# APRSTracker.net
KiCad netlist of a schematic drawn in EAGLE
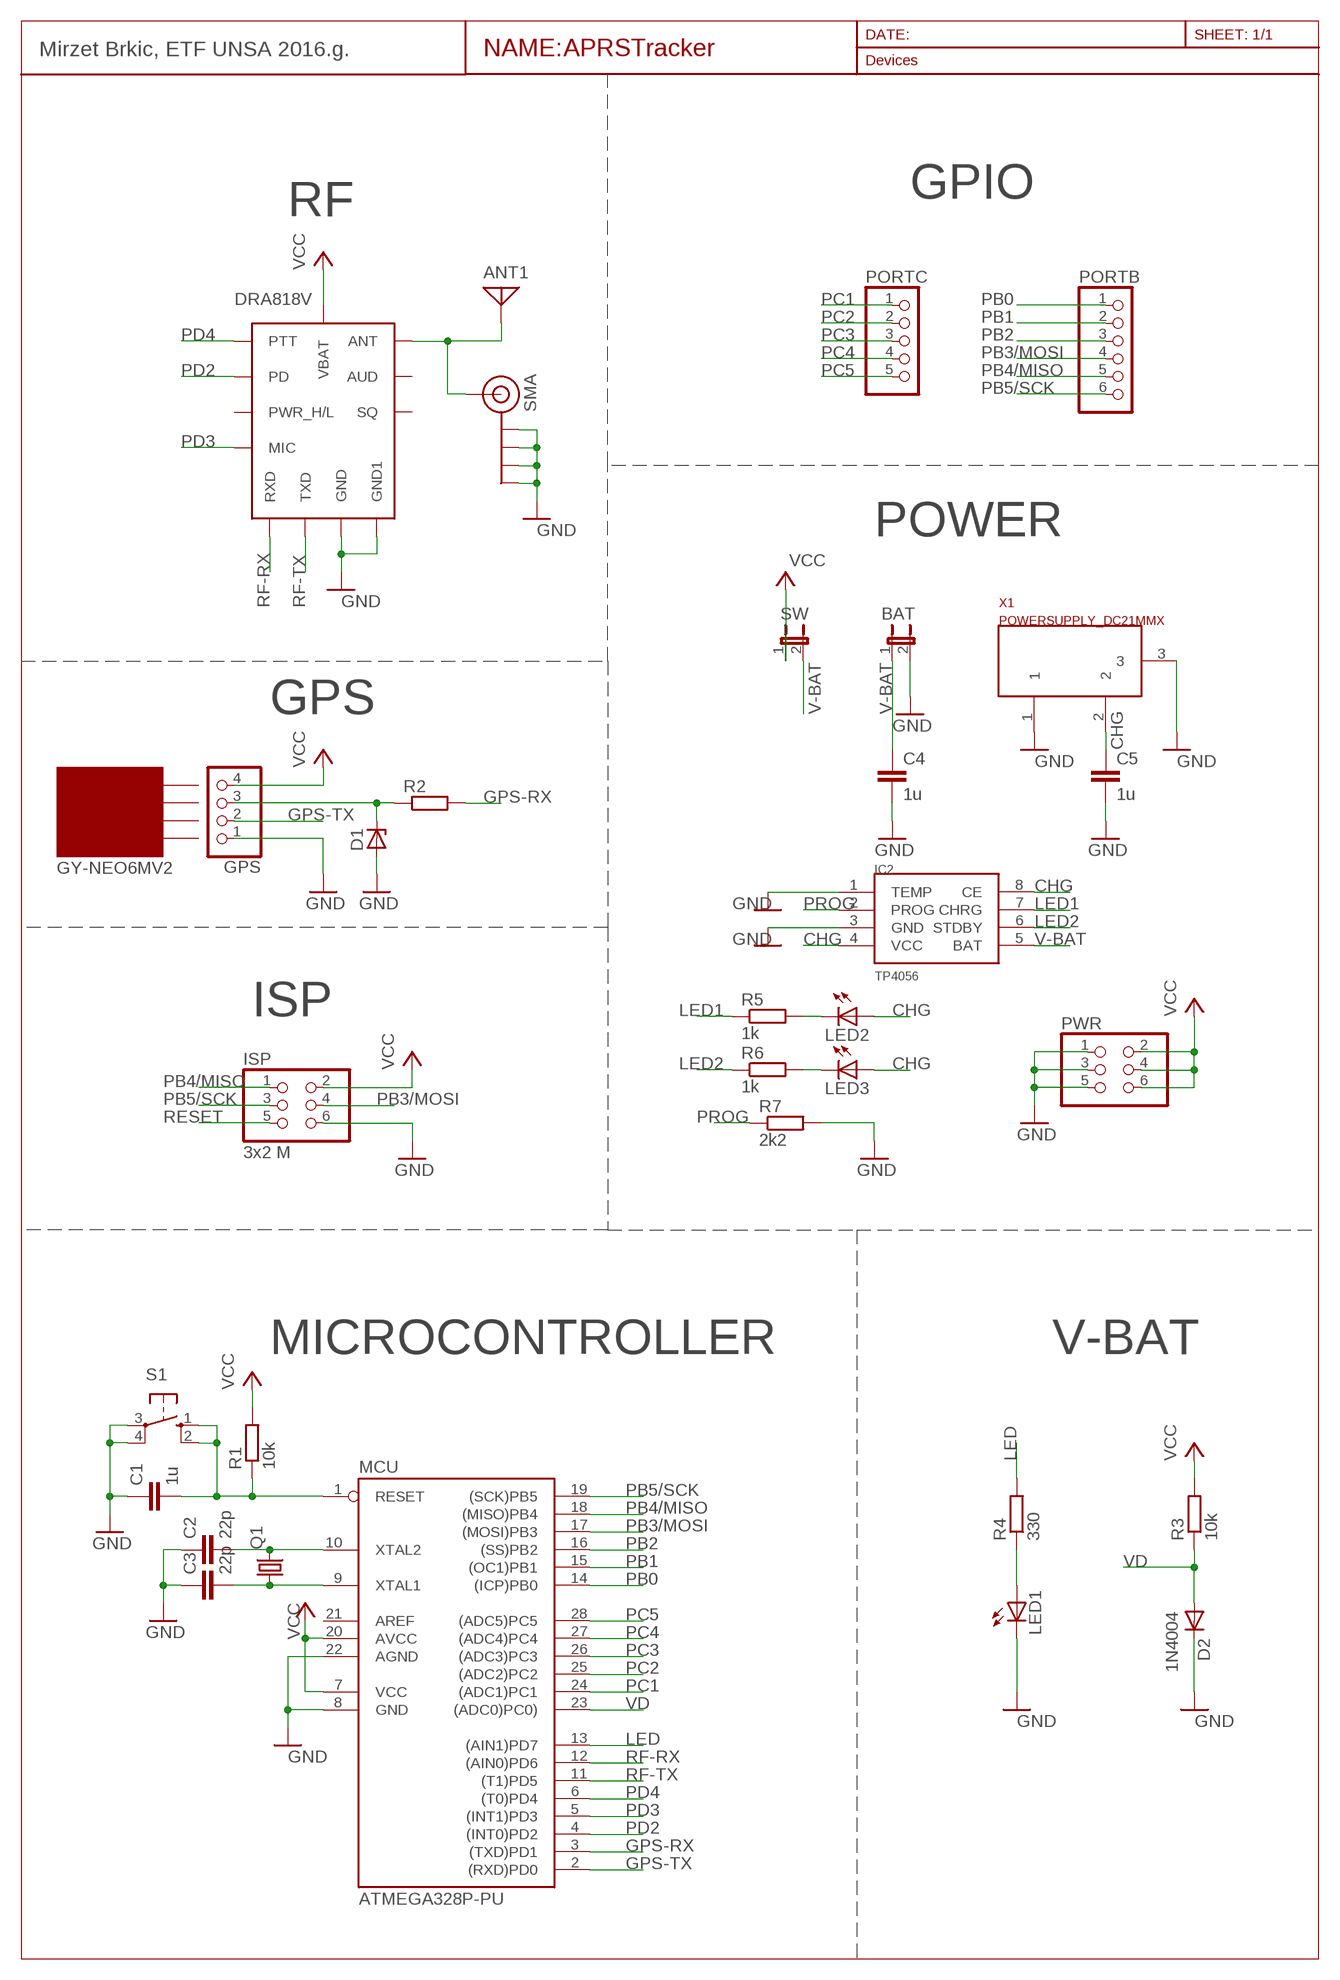
[diagram p0: schematic, sheet 1]

(export (version "E")
  (design (tool "Eeschema 10.0.6"))
  (components
    (comp (ref "ANT1")
      (value "ANTENNA")
      (footprint "eagle-import:PAD-01")
      (libsource (lib "eagle-import") (part "ANTENNA"))
    )
    (comp (ref "BAT")
      (value "JP1E")
      (footprint "eagle-import:JP1")
      (libsource (lib "eagle-import") (part "JP1E"))
    )
    (comp (ref "C1")
      (value "1u")
      (footprint "eagle-import:C050-024X044")
      (libsource (lib "eagle-import") (part "C-EU050-024X044"))
    )
    (comp (ref "C2")
      (value "22p")
      (footprint "eagle-import:C025-024X044")
      (libsource (lib "eagle-import") (part "C-EU025-024X044"))
    )
    (comp (ref "C3")
      (value "22p")
      (footprint "eagle-import:C025-024X044")
      (libsource (lib "eagle-import") (part "C-EU025-024X044"))
    )
    (comp (ref "C4")
      (value "1u")
      (footprint "eagle-import:C050-024X044")
      (libsource (lib "eagle-import") (part "C-EU050-024X044"))
    )
    (comp (ref "C5")
      (value "1u")
      (footprint "eagle-import:C050-024X044")
      (libsource (lib "eagle-import") (part "C-EU050-024X044"))
    )
    (comp (ref "D1")
      (value "ZENER-DIODEDO35Z10")
      (footprint "eagle-import:DO35Z10")
      (libsource (lib "eagle-import") (part "ZENER-DIODEDO35Z10"))
    )
    (comp (ref "D2")
      (value "1N4004")
      (footprint "eagle-import:DO41-10")
      (libsource (lib "eagle-import") (part "1N4004"))
    )
    (comp (ref "DRA818V")
      (value "DRA818V")
      (footprint "eagle-import:DRA8XXZ")
      (libsource (lib "eagle-import") (part "DRA818V"))
    )
    (comp (ref "GPS")
      (value "PINHD-1X4")
      (footprint "eagle-import:1X04")
      (libsource (lib "eagle-import") (part "PINHD-1X4"))
    )
    (comp (ref "IC2")
      (value "TP4056")
      (footprint "eagle-import:SOP-8")
      (libsource (lib "eagle-import") (part "TP4056"))
    )
    (comp (ref "ISP")
      (value "3x2 M")
      (footprint "eagle-import:2X03")
      (libsource (lib "eagle-import") (part "PINHD-2X3"))
    )
    (comp (ref "LED1")
      (value "LED3MM")
      (footprint "eagle-import:LED3MM")
      (libsource (lib "eagle-import") (part "LED3MM"))
    )
    (comp (ref "LED2")
      (value "LED3MM")
      (footprint "eagle-import:LED3MM")
      (libsource (lib "eagle-import") (part "LED3MM"))
    )
    (comp (ref "LED3")
      (value "LED3MM")
      (footprint "eagle-import:LED3MM")
      (libsource (lib "eagle-import") (part "LED3MM"))
    )
    (comp (ref "MCU")
      (value "ATMEGA328P-PU")
      (footprint "eagle-import:DIL28-3")
      (libsource (lib "eagle-import") (part "ATMEGA328P-PU"))
    )
    (comp (ref "PORTB")
      (value "PINHD-1X6")
      (footprint "eagle-import:1X06")
      (libsource (lib "eagle-import") (part "PINHD-1X6"))
    )
    (comp (ref "PORTC")
      (value "PINHD-1X5")
      (footprint "eagle-import:1X05")
      (libsource (lib "eagle-import") (part "PINHD-1X5"))
    )
    (comp (ref "PWR")
      (value "PINHD-2X3")
      (footprint "eagle-import:2X03")
      (libsource (lib "eagle-import") (part "pinhead_PINHD-2X3"))
    )
    (comp (ref "Q1")
      (value "CRYSTALHC49S")
      (footprint "eagle-import:HC49_S")
      (libsource (lib "eagle-import") (part "CRYSTALHC49S"))
    )
    (comp (ref "R1")
      (value "10k")
      (footprint "eagle-import:0207_10")
      (libsource (lib "eagle-import") (part "R-EU_0207/10"))
    )
    (comp (ref "R2")
      (value "R-EU_0207/10")
      (footprint "eagle-import:0207_10")
      (libsource (lib "eagle-import") (part "R-EU_0207/10"))
    )
    (comp (ref "R3")
      (value "10k")
      (footprint "eagle-import:0207_10")
      (libsource (lib "eagle-import") (part "R-EU_0207/10"))
    )
    (comp (ref "R4")
      (value "330")
      (footprint "eagle-import:0207_10")
      (libsource (lib "eagle-import") (part "R-EU_0207/10"))
    )
    (comp (ref "R5")
      (value "1k")
      (footprint "eagle-import:0207_10")
      (libsource (lib "eagle-import") (part "R-EU_0207/10"))
    )
    (comp (ref "R6")
      (value "1k")
      (footprint "eagle-import:0207_10")
      (libsource (lib "eagle-import") (part "R-EU_0207/10"))
    )
    (comp (ref "R7")
      (value "2k2")
      (footprint "eagle-import:0207_10")
      (libsource (lib "eagle-import") (part "R-EU_0207/10"))
    )
    (comp (ref "S1")
      (value "10-XX")
      (footprint "eagle-import:B3F-10XX")
      (fields (field (name "MPN") "B3F-1000"))
      (libsource (lib "eagle-import") (part "10-XX"))
    )
    (comp (ref "SMA")
      (value "SMA_EDGE")
      (footprint "eagle-import:SMA-EDGE")
      (libsource (lib "eagle-import") (part "SMA_EDGE"))
    )
    (comp (ref "SW")
      (value "JP1E")
      (footprint "eagle-import:JP1")
      (libsource (lib "eagle-import") (part "JP1E"))
    )
    (comp (ref "X1")
      (value "POWERSUPPLY_DC21MMX")
      (footprint "eagle-import:POWERSUPPLY_DC-21MM")
      (libsource (lib "eagle-import") (part "POWERSUPPLY_DC21MMX"))
    )
  )
  (nets
    (net (code "1") (name "/CHG") (class "Default")
      (node (ref "C5") (pin "1") (pinfunction "1_1") (pintype "passive"))
      (node (ref "IC2") (pin "4") (pinfunction "VCC_4") (pintype "bidirectional"))
      (node (ref "IC2") (pin "8") (pinfunction "CE_8") (pintype "bidirectional"))
      (node (ref "LED2") (pin "A") (pinfunction "A_A") (pintype "passive"))
      (node (ref "LED3") (pin "A") (pinfunction "A_A") (pintype "passive"))
      (node (ref "X1") (pin "2") (pinfunction "2_2") (pintype "power_in"))
    )
    (net (code "2") (name "/GPS-RX") (class "Default")
      (node (ref "MCU") (pin "3") (pinfunction "(TXD)PD1_3") (pintype "bidirectional"))
      (node (ref "R2") (pin "2") (pinfunction "2_2") (pintype "passive"))
    )
    (net (code "3") (name "/GPS-TX") (class "Default")
      (node (ref "GPS") (pin "2") (pinfunction "2_2") (pintype "passive"))
      (node (ref "MCU") (pin "2") (pinfunction "(RXD)PD0_2") (pintype "bidirectional"))
    )
    (net (code "4") (name "/LED") (class "Default")
      (node (ref "MCU") (pin "13") (pinfunction "(AIN1)PD7_13") (pintype "bidirectional"))
      (node (ref "R4") (pin "2") (pinfunction "2_2") (pintype "passive"))
    )
    (net (code "5") (name "/LED1") (class "Default")
      (node (ref "IC2") (pin "7") (pinfunction "CHRG_7") (pintype "bidirectional"))
      (node (ref "R5") (pin "1") (pinfunction "1_1") (pintype "passive"))
    )
    (net (code "6") (name "/LED2") (class "Default")
      (node (ref "IC2") (pin "6") (pinfunction "STDBY_6") (pintype "bidirectional"))
      (node (ref "R6") (pin "1") (pinfunction "1_1") (pintype "passive"))
    )
    (net (code "7") (name "/PB0") (class "Default")
      (node (ref "MCU") (pin "14") (pinfunction "(ICP)PB0_14") (pintype "bidirectional"))
      (node (ref "PORTB") (pin "1") (pinfunction "1_1") (pintype "passive"))
    )
    (net (code "8") (name "/PB1") (class "Default")
      (node (ref "MCU") (pin "15") (pinfunction "(OC1)PB1_15") (pintype "bidirectional"))
      (node (ref "PORTB") (pin "2") (pinfunction "2_2") (pintype "passive"))
    )
    (net (code "9") (name "/PB2") (class "Default")
      (node (ref "MCU") (pin "16") (pinfunction "(SS)PB2_16") (pintype "bidirectional"))
      (node (ref "PORTB") (pin "3") (pinfunction "3_3") (pintype "passive"))
    )
    (net (code "10") (name "/PB3{slash}MOSI") (class "Default")
      (node (ref "ISP") (pin "4") (pinfunction "4_4") (pintype "passive"))
      (node (ref "MCU") (pin "17") (pinfunction "(MOSI)PB3_17") (pintype "bidirectional"))
      (node (ref "PORTB") (pin "4") (pinfunction "4_4") (pintype "passive"))
    )
    (net (code "11") (name "/PB4{slash}MISO") (class "Default")
      (node (ref "ISP") (pin "1") (pinfunction "1_1") (pintype "passive"))
      (node (ref "MCU") (pin "18") (pinfunction "(MISO)PB4_18") (pintype "bidirectional"))
      (node (ref "PORTB") (pin "5") (pinfunction "5_5") (pintype "passive"))
    )
    (net (code "12") (name "/PB5{slash}SCK") (class "Default")
      (node (ref "ISP") (pin "3") (pinfunction "3_3") (pintype "passive"))
      (node (ref "MCU") (pin "19") (pinfunction "(SCK)PB5_19") (pintype "bidirectional"))
      (node (ref "PORTB") (pin "6") (pinfunction "6_6") (pintype "passive"))
    )
    (net (code "13") (name "/PC1") (class "Default")
      (node (ref "MCU") (pin "24") (pinfunction "(ADC1)PC1_24") (pintype "bidirectional"))
      (node (ref "PORTC") (pin "1") (pinfunction "1_1") (pintype "passive"))
    )
    (net (code "14") (name "/PC2") (class "Default")
      (node (ref "MCU") (pin "25") (pinfunction "(ADC2)PC2_25") (pintype "bidirectional"))
      (node (ref "PORTC") (pin "2") (pinfunction "2_2") (pintype "passive"))
    )
    (net (code "15") (name "/PC3") (class "Default")
      (node (ref "MCU") (pin "26") (pinfunction "(ADC3)PC3_26") (pintype "bidirectional"))
      (node (ref "PORTC") (pin "3") (pinfunction "3_3") (pintype "passive"))
    )
    (net (code "16") (name "/PC4") (class "Default")
      (node (ref "MCU") (pin "27") (pinfunction "(ADC4)PC4_27") (pintype "bidirectional"))
      (node (ref "PORTC") (pin "4") (pinfunction "4_4") (pintype "passive"))
    )
    (net (code "17") (name "/PC5") (class "Default")
      (node (ref "MCU") (pin "28") (pinfunction "(ADC5)PC5_28") (pintype "bidirectional"))
      (node (ref "PORTC") (pin "5") (pinfunction "5_5") (pintype "passive"))
    )
    (net (code "18") (name "/PD2") (class "Default")
      (node (ref "DRA818V") (pin "P$6") (pinfunction "PD_P$6") (pintype "bidirectional"))
      (node (ref "MCU") (pin "4") (pinfunction "(INT0)PD2_4") (pintype "bidirectional"))
    )
    (net (code "19") (name "/PD3") (class "Default")
      (node (ref "DRA818V") (pin "P$18") (pinfunction "MIC_P$18") (pintype "bidirectional"))
      (node (ref "MCU") (pin "5") (pinfunction "(INT1)PD3_5") (pintype "bidirectional"))
    )
    (net (code "20") (name "/PD4") (class "Default")
      (node (ref "DRA818V") (pin "P$5") (pinfunction "PTT_P$5") (pintype "bidirectional"))
      (node (ref "MCU") (pin "6") (pinfunction "(T0)PD4_6") (pintype "bidirectional"))
    )
    (net (code "21") (name "/PROG") (class "Default")
      (node (ref "IC2") (pin "2") (pinfunction "PROG_2") (pintype "bidirectional"))
      (node (ref "R7") (pin "1") (pinfunction "1_1") (pintype "passive"))
    )
    (net (code "22") (name "/RESET") (class "Default")
      (node (ref "C1") (pin "2") (pinfunction "2_2") (pintype "passive"))
      (node (ref "ISP") (pin "5") (pinfunction "5_5") (pintype "passive"))
      (node (ref "MCU") (pin "1") (pinfunction "RESET_1") (pintype "input"))
      (node (ref "R1") (pin "1") (pinfunction "1_1") (pintype "passive"))
      (node (ref "S1") (pin "1") (pinfunction "S_1") (pintype "passive"))
      (node (ref "S1") (pin "2") (pinfunction "S1_2") (pintype "passive"))
    )
    (net (code "23") (name "/RF-RX") (class "Default")
      (node (ref "DRA818V") (pin "P$16") (pinfunction "RXD_P$16") (pintype "bidirectional"))
      (node (ref "MCU") (pin "12") (pinfunction "(AIN0)PD6_12") (pintype "bidirectional"))
    )
    (net (code "24") (name "/RF-TX") (class "Default")
      (node (ref "DRA818V") (pin "P$17") (pinfunction "TXD_P$17") (pintype "bidirectional"))
      (node (ref "MCU") (pin "11") (pinfunction "(T1)PD5_11") (pintype "bidirectional"))
    )
    (net (code "25") (name "/V-BAT") (class "Default")
      (node (ref "BAT") (pin "1") (pinfunction "1_1") (pintype "passive"))
      (node (ref "C4") (pin "1") (pinfunction "1_1") (pintype "passive"))
      (node (ref "IC2") (pin "5") (pinfunction "BAT_5") (pintype "bidirectional"))
      (node (ref "SW") (pin "2") (pinfunction "2_2") (pintype "passive"))
    )
    (net (code "26") (name "/VD") (class "Default")
      (node (ref "D2") (pin "A") (pinfunction "A_A") (pintype "passive"))
      (node (ref "MCU") (pin "23") (pinfunction "(ADC0)PC0)_23") (pintype "bidirectional"))
      (node (ref "R3") (pin "1") (pinfunction "1_1") (pintype "passive"))
    )
    (net (code "27") (name "GND") (class "Default")
      (node (ref "BAT") (pin "2") (pinfunction "2_2") (pintype "passive"))
      (node (ref "C1") (pin "1") (pinfunction "1_1") (pintype "passive"))
      (node (ref "C2") (pin "1") (pinfunction "1_1") (pintype "passive"))
      (node (ref "C3") (pin "1") (pinfunction "1_1") (pintype "passive"))
      (node (ref "C4") (pin "2") (pinfunction "2_2") (pintype "passive"))
      (node (ref "C5") (pin "2") (pinfunction "2_2") (pintype "passive"))
      (node (ref "D1") (pin "A") (pinfunction "A_A") (pintype "passive"))
      (node (ref "D2") (pin "C") (pinfunction "C_C") (pintype "passive"))
      (node (ref "DRA818V") (pin "P$10") (pinfunction "GND1_P$10") (pintype "bidirectional"))
      (node (ref "DRA818V") (pin "P$9") (pinfunction "GND_P$9") (pintype "bidirectional"))
      (node (ref "GPS") (pin "1") (pinfunction "1_1") (pintype "passive"))
      (node (ref "IC2") (pin "1") (pinfunction "TEMP_1") (pintype "bidirectional"))
      (node (ref "IC2") (pin "3") (pinfunction "GND_3") (pintype "bidirectional"))
      (node (ref "ISP") (pin "6") (pinfunction "6_6") (pintype "passive"))
      (node (ref "LED1") (pin "K") (pinfunction "C_K") (pintype "passive"))
      (node (ref "MCU") (pin "22") (pinfunction "AGND_22") (pintype "power_in"))
      (node (ref "MCU") (pin "8") (pinfunction "GND_8") (pintype "power_in"))
      (node (ref "PWR") (pin "1") (pinfunction "1_1") (pintype "passive"))
      (node (ref "PWR") (pin "3") (pinfunction "3_3") (pintype "passive"))
      (node (ref "PWR") (pin "5") (pinfunction "5_5") (pintype "passive"))
      (node (ref "R7") (pin "2") (pinfunction "2_2") (pintype "passive"))
      (node (ref "S1") (pin "3") (pinfunction "P_3") (pintype "passive"))
      (node (ref "S1") (pin "4") (pinfunction "P1_4") (pintype "passive"))
      (node (ref "SMA") (pin "GND@0") (pinfunction "GND_GND@0") (pintype "bidirectional"))
      (node (ref "SMA") (pin "GND@1") (pinfunction "GND_GND@1") (pintype "bidirectional"))
      (node (ref "SMA") (pin "GND@2") (pinfunction "GND_GND@2") (pintype "bidirectional"))
      (node (ref "SMA") (pin "GND@3") (pinfunction "GND_GND@3") (pintype "bidirectional"))
      (node (ref "X1") (pin "1") (pinfunction "1_1") (pintype "power_in"))
      (node (ref "X1") (pin "3") (pinfunction "3_3") (pintype "power_in"))
    )
    (net (code "28") (name "Net-(D1-PadC)") (class "Default")
      (node (ref "D1") (pin "C") (pinfunction "C_C") (pintype "passive"))
      (node (ref "GPS") (pin "3") (pinfunction "3_3") (pintype "passive"))
      (node (ref "R2") (pin "1") (pinfunction "1_1") (pintype "passive"))
    )
    (net (code "29") (name "Net-(DRA818V-ANT)") (class "Default")
      (node (ref "ANT1") (pin "1") (pinfunction "1_1") (pintype "output"))
      (node (ref "DRA818V") (pin "P$12") (pinfunction "ANT_P$12") (pintype "bidirectional"))
      (node (ref "SMA") (pin "SIG") (pinfunction "SIGNAL_SIG") (pintype "bidirectional"))
    )
    (net (code "30") (name "Net-(LED1-PadA)") (class "Default")
      (node (ref "LED1") (pin "A") (pinfunction "A_A") (pintype "passive"))
      (node (ref "R4") (pin "1") (pinfunction "1_1") (pintype "passive"))
    )
    (net (code "31") (name "Net-(LED2-C)") (class "Default")
      (node (ref "LED2") (pin "K") (pinfunction "C_K") (pintype "passive"))
      (node (ref "R5") (pin "2") (pinfunction "2_2") (pintype "passive"))
    )
    (net (code "32") (name "Net-(LED3-C)") (class "Default")
      (node (ref "LED3") (pin "K") (pinfunction "C_K") (pintype "passive"))
      (node (ref "R6") (pin "2") (pinfunction "2_2") (pintype "passive"))
    )
    (net (code "33") (name "Net-(MCU-XTAL1)") (class "Default")
      (node (ref "C3") (pin "2") (pinfunction "2_2") (pintype "passive"))
      (node (ref "MCU") (pin "9") (pinfunction "XTAL1_9") (pintype "bidirectional"))
      (node (ref "Q1") (pin "1") (pinfunction "1_1") (pintype "passive"))
    )
    (net (code "34") (name "Net-(MCU-XTAL2)") (class "Default")
      (node (ref "C2") (pin "2") (pinfunction "2_2") (pintype "passive"))
      (node (ref "MCU") (pin "10") (pinfunction "XTAL2_10") (pintype "bidirectional"))
      (node (ref "Q1") (pin "2") (pinfunction "2_2") (pintype "passive"))
    )
    (net (code "35") (name "VCC") (class "Default")
      (node (ref "DRA818V") (pin "P$8") (pinfunction "VBAT_P$8") (pintype "bidirectional"))
      (node (ref "GPS") (pin "4") (pinfunction "4_4") (pintype "passive"))
      (node (ref "ISP") (pin "2") (pinfunction "2_2") (pintype "passive"))
      (node (ref "MCU") (pin "20") (pinfunction "AVCC_20") (pintype "power_in"))
      (node (ref "MCU") (pin "7") (pinfunction "VCC_7") (pintype "power_in"))
      (node (ref "PWR") (pin "2") (pinfunction "2_2") (pintype "passive"))
      (node (ref "PWR") (pin "4") (pinfunction "4_4") (pintype "passive"))
      (node (ref "PWR") (pin "6") (pinfunction "6_6") (pintype "passive"))
      (node (ref "R1") (pin "2") (pinfunction "2_2") (pintype "passive"))
      (node (ref "R3") (pin "2") (pinfunction "2_2") (pintype "passive"))
      (node (ref "SW") (pin "1") (pinfunction "1_1") (pintype "passive"))
    )
    (net (code "36") (name "unconnected-(DRA818V-AUD-PadP$3)") (class "Default")
      (node (ref "DRA818V") (pin "P$3") (pinfunction "AUD_P$3") (pintype "bidirectional"))
    )
    (net (code "37") (name "unconnected-(DRA818V-PWR_H{slash}L-PadP$7)") (class "Default")
      (node (ref "DRA818V") (pin "P$7") (pinfunction "PWR_H/L_P$7") (pintype "bidirectional"))
    )
    (net (code "38") (name "unconnected-(DRA818V-SQ-PadP$1)") (class "Default")
      (node (ref "DRA818V") (pin "P$1") (pinfunction "SQ_P$1") (pintype "bidirectional"))
    )
    (net (code "39") (name "unconnected-(MCU-AREF-Pad21)") (class "Default")
      (node (ref "MCU") (pin "21") (pinfunction "AREF_21") (pintype "passive"))
    )
  )
)
